# Connectors.net
KiCad netlist of a schematic drawn in Altium Designer
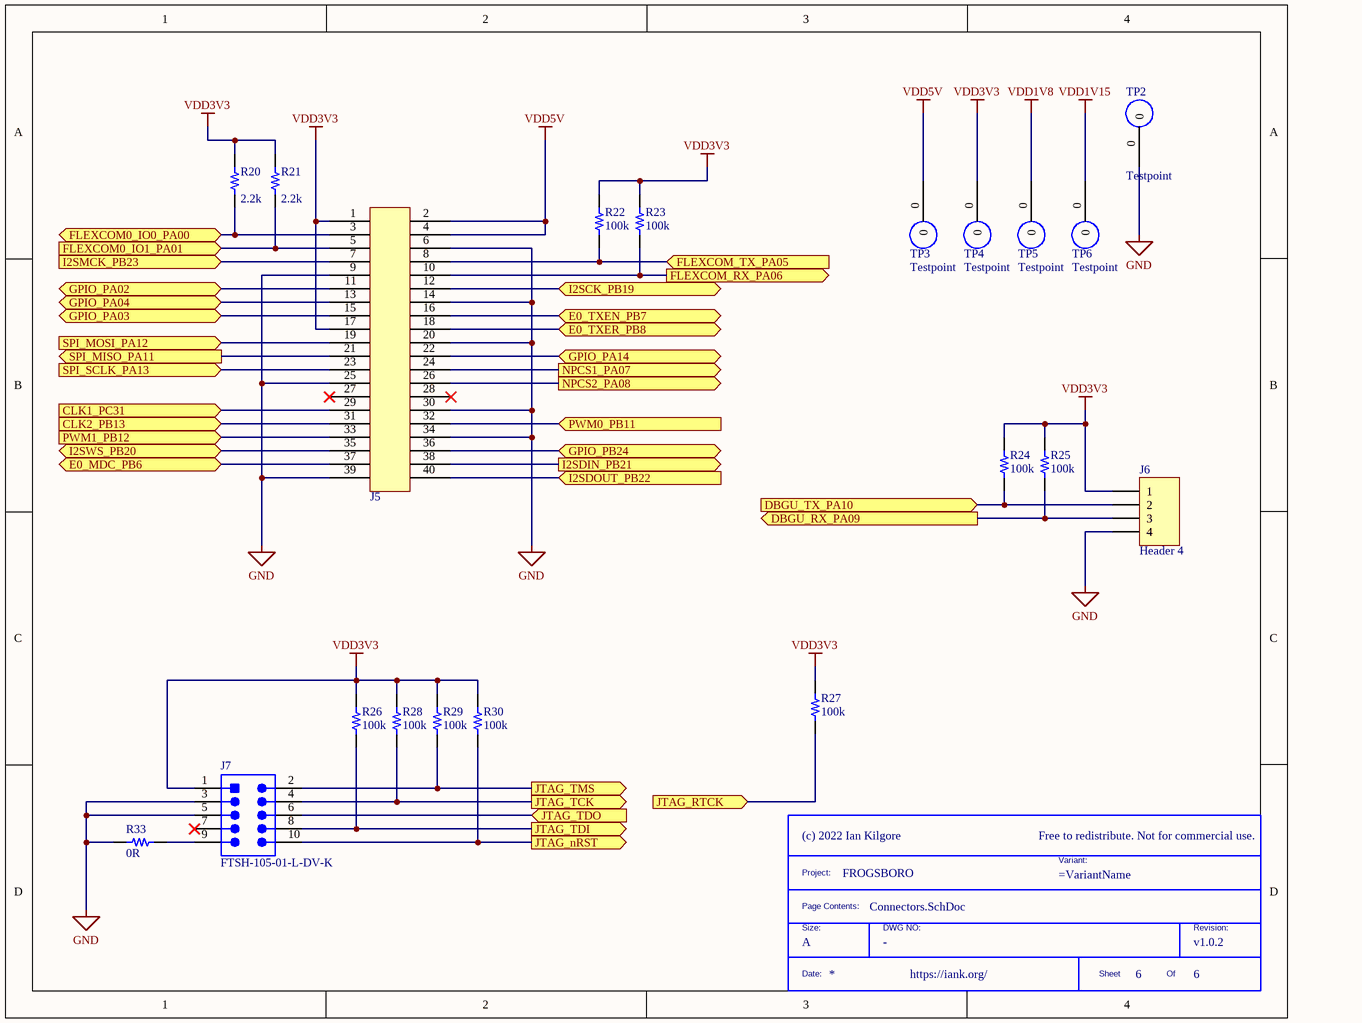
[diagram p0: Connectors.SchDoc]

(export (version "E")
  (design (tool "Eeschema 10.0.6"))
  (components
    (comp (ref "J5")
      (value "DF23C-40DP-0.5V(92)")
      (footprint "FROGSBORO:DF23C-40DP-0.5V(92)")
      (description "0.5mm Pitch Low-Profile (H=1.5mm) Board to Board / FPC to Board Connectors")
      (fields (field (name "MANUFACTURER") "Hirose"))
      (libsource (lib "FROGSBORO") (part "DF23C-40DP-0.5V(92)"))
    )
    (comp (ref "J6")
      (value "Header 4")
      (footprint "HDR1X4")
      (description "Header, 4-Pin")
      (fields (field (name "PUBLISHER") "Altium Limited"))
      (libsource (lib "Miscellaneous Connectors") (part "Header 4"))
    )
    (comp (ref "J7")
      (value "FTSH-105-01-L-DV-K")
      (footprint "SMTC-FTSH-105-01-L-DV-K_V")
      (description "Male Header, Pitch 1.27 mm, 2 x 5 Position, Height 6.25 mm")
      (fields (field (name "MANUFACTURER") "Samtec"))
      (libsource (lib "Altium Content Vault") (part "CN-2P-M-R10"))
    )
    (comp (ref "R20")
      (value "2.2k")
      (footprint "RES 0402_1005")
      (description "RES SMD 2.2K OHM 1% 1/5W 0402")
      (fields (field (name "PART NUMBER") "RCS04022K20FKED"))
      (libsource (lib "Celestial Altium Library - altium_library") (part "Resistor"))
    )
    (comp (ref "R21")
      (value "2.2k")
      (footprint "RES 0402_1005")
      (description "RES SMD 2.2K OHM 1% 1/5W 0402")
      (fields (field (name "PART NUMBER") "RCS04022K20FKED"))
      (libsource (lib "Celestial Altium Library - altium_library") (part "Resistor"))
    )
    (comp (ref "R22")
      (value "100k")
      (footprint "RES 0402_1005")
      (description "RES SMD 100K OHM 1% 1/16W 0402")
      (fields (field (name "PART NUMBER") "CRCW0402100KFKEDC") (field (name "MANUFACTURER") "Vishay Dale"))
      (libsource (lib "Celestial Altium Library - altium_library") (part "Resistor"))
    )
    (comp (ref "R23")
      (value "100k")
      (footprint "RES 0402_1005")
      (description "RES SMD 100K OHM 1% 1/16W 0402")
      (fields (field (name "PART NUMBER") "CRCW0402100KFKEDC") (field (name "MANUFACTURER") "Vishay Dale"))
      (libsource (lib "Celestial Altium Library - altium_library") (part "Resistor"))
    )
    (comp (ref "R24")
      (value "100k")
      (footprint "RES 0402_1005")
      (description "RES SMD 100K OHM 1% 1/16W 0402")
      (fields (field (name "PART NUMBER") "CRCW0402100KFKEDC") (field (name "MANUFACTURER") "Vishay Dale"))
      (libsource (lib "Celestial Altium Library - altium_library") (part "Resistor"))
    )
    (comp (ref "R25")
      (value "100k")
      (footprint "RES 0402_1005")
      (description "RES SMD 100K OHM 1% 1/16W 0402")
      (fields (field (name "PART NUMBER") "CRCW0402100KFKEDC") (field (name "MANUFACTURER") "Vishay Dale"))
      (libsource (lib "Celestial Altium Library - altium_library") (part "Resistor"))
    )
    (comp (ref "R26")
      (value "100k")
      (footprint "RES 0402_1005")
      (description "RES SMD 100K OHM 1% 1/16W 0402")
      (fields (field (name "PART NUMBER") "CRCW0402100KFKEDC") (field (name "MANUFACTURER") "Vishay Dale"))
      (libsource (lib "Celestial Altium Library - altium_library") (part "Resistor"))
    )
    (comp (ref "R27")
      (value "100k")
      (footprint "RES 0402_1005")
      (description "RES SMD 100K OHM 1% 1/16W 0402")
      (fields (field (name "PART NUMBER") "CRCW0402100KFKEDC") (field (name "MANUFACTURER") "Vishay Dale"))
      (libsource (lib "Celestial Altium Library - altium_library") (part "Resistor"))
    )
    (comp (ref "R28")
      (value "100k")
      (footprint "RES 0402_1005")
      (description "RES SMD 100K OHM 1% 1/16W 0402")
      (fields (field (name "PART NUMBER") "CRCW0402100KFKEDC") (field (name "MANUFACTURER") "Vishay Dale"))
      (libsource (lib "Celestial Altium Library - altium_library") (part "Resistor"))
    )
    (comp (ref "R29")
      (value "100k")
      (footprint "RES 0402_1005")
      (description "RES SMD 100K OHM 1% 1/16W 0402")
      (fields (field (name "PART NUMBER") "CRCW0402100KFKEDC") (field (name "MANUFACTURER") "Vishay Dale"))
      (libsource (lib "Celestial Altium Library - altium_library") (part "Resistor"))
    )
    (comp (ref "R30")
      (value "100k")
      (footprint "RES 0402_1005")
      (description "RES SMD 100K OHM 1% 1/16W 0402")
      (fields (field (name "PART NUMBER") "CRCW0402100KFKEDC") (field (name "MANUFACTURER") "Vishay Dale"))
      (libsource (lib "Celestial Altium Library - altium_library") (part "Resistor"))
    )
    (comp (ref "R33")
      (value "0R")
      (footprint "RES 0402_1005")
      (description "RES SMD 0 OHM JUMPER 1/16W 0402")
      (fields
        (field (name "PART NUMBER") "CRG0402ZR")
        (field (name "MANUFACTURER") "TE Connectivity Passive Product")
      )
      (libsource (lib "Celestial Altium Library - altium_library") (part "Resistor"))
    )
    (comp (ref "TP2")
      (value "Testpoint")
      (footprint "FROGSBORO:Testpoint")
      (libsource (lib "FROGSBORO") (part "Testpoint"))
    )
    (comp (ref "TP3")
      (value "Testpoint")
      (footprint "FROGSBORO:Testpoint")
      (libsource (lib "FROGSBORO") (part "Testpoint"))
    )
    (comp (ref "TP4")
      (value "Testpoint")
      (footprint "FROGSBORO:Testpoint")
      (libsource (lib "FROGSBORO") (part "Testpoint"))
    )
    (comp (ref "TP5")
      (value "Testpoint")
      (footprint "FROGSBORO:Testpoint")
      (libsource (lib "FROGSBORO") (part "Testpoint"))
    )
    (comp (ref "TP6")
      (value "Testpoint")
      (footprint "FROGSBORO:Testpoint")
      (libsource (lib "FROGSBORO") (part "Testpoint"))
    )
  )
  (nets
    (net (code "1") (name "/CLK1_PC31") (class "Default") (node (ref "J5") (pin "29") (pintype "passive")))
    (net (code "2") (name "/CLK2_PB13") (class "Default") (node (ref "J5") (pin "31") (pintype "passive")))
    (net (code "3") (name "/DBGU_RX_PA09") (class "Default")
      (node (ref "J6") (pin "3") (pinfunction "3_3") (pintype "passive"))
      (node (ref "R25") (pin "1") (pinfunction "1_1") (pintype "passive"))
    )
    (net (code "4") (name "/DBGU_TX_PA10") (class "Default")
      (node (ref "J6") (pin "2") (pinfunction "2_2") (pintype "passive"))
      (node (ref "R24") (pin "1") (pinfunction "1_1") (pintype "passive"))
    )
    (net (code "5") (name "/E0_MDC_PB6") (class "Default") (node (ref "J5") (pin "37") (pintype "passive")))
    (net (code "6") (name "/E0_TXEN_PB7") (class "Default") (node (ref "J5") (pin "16") (pintype "passive")))
    (net (code "7") (name "/E0_TXER_PB8") (class "Default") (node (ref "J5") (pin "18") (pintype "passive")))
    (net (code "8") (name "/FLEXCOM0_IO0_PA00") (class "Default")
      (node (ref "J5") (pin "3") (pintype "passive"))
      (node (ref "R20") (pin "1") (pinfunction "1_1") (pintype "passive"))
    )
    (net (code "9") (name "/FLEXCOM0_IO1_PA01") (class "Default")
      (node (ref "J5") (pin "5") (pintype "passive"))
      (node (ref "R21") (pin "1") (pinfunction "1_1") (pintype "passive"))
    )
    (net (code "10") (name "/FLEXCOM_RX_PA06") (class "Default")
      (node (ref "J5") (pin "10") (pintype "passive"))
      (node (ref "R23") (pin "1") (pinfunction "1_1") (pintype "passive"))
    )
    (net (code "11") (name "/FLEXCOM_TX_PA05") (class "Default")
      (node (ref "J5") (pin "8") (pintype "passive"))
      (node (ref "R22") (pin "1") (pinfunction "1_1") (pintype "passive"))
    )
    (net (code "12") (name "/GPIO_PA02") (class "Default") (node (ref "J5") (pin "11") (pintype "passive")))
    (net (code "13") (name "/GPIO_PA03") (class "Default") (node (ref "J5") (pin "15") (pintype "passive")))
    (net (code "14") (name "/GPIO_PA04") (class "Default") (node (ref "J5") (pin "13") (pintype "passive")))
    (net (code "15") (name "/GPIO_PA14") (class "Default") (node (ref "J5") (pin "22") (pintype "passive")))
    (net (code "16") (name "/GPIO_PB24") (class "Default") (node (ref "J5") (pin "36") (pintype "passive")))
    (net (code "17") (name "/I2SCK_PB19") (class "Default") (node (ref "J5") (pin "12") (pintype "passive")))
    (net (code "18") (name "/I2SDIN_PB21") (class "Default") (node (ref "J5") (pin "38") (pintype "passive")))
    (net (code "19") (name "/I2SDOUT_PB22") (class "Default")
      (node (ref "J5") (pin "40") (pintype "passive"))
    )
    (net (code "20") (name "/I2SMCK_PB23") (class "Default") (node (ref "J5") (pin "7") (pintype "passive")))
    (net (code "21") (name "/I2SWS_PB20") (class "Default") (node (ref "J5") (pin "35") (pintype "passive")))
    (net (code "22") (name "/JTAG_RTCK") (class "Default")
      (node (ref "R27") (pin "1") (pinfunction "1_1") (pintype "passive"))
    )
    (net (code "23") (name "/JTAG_TCK") (class "Default")
      (node (ref "J7") (pin "4") (pinfunction "4_4") (pintype "passive"))
      (node (ref "R28") (pin "1") (pinfunction "1_1") (pintype "passive"))
    )
    (net (code "24") (name "/JTAG_TDI") (class "Default")
      (node (ref "J7") (pin "8") (pinfunction "8_8") (pintype "passive"))
      (node (ref "R26") (pin "1") (pinfunction "1_1") (pintype "passive"))
    )
    (net (code "25") (name "/JTAG_TDO") (class "Default")
      (node (ref "J7") (pin "6") (pinfunction "6_6") (pintype "passive"))
    )
    (net (code "26") (name "/JTAG_TMS") (class "Default")
      (node (ref "J7") (pin "2") (pinfunction "2_2") (pintype "passive"))
      (node (ref "R29") (pin "1") (pinfunction "1_1") (pintype "passive"))
    )
    (net (code "27") (name "/JTAG_nRST") (class "Default")
      (node (ref "J7") (pin "10") (pinfunction "10_10") (pintype "passive"))
      (node (ref "R30") (pin "1") (pinfunction "1_1") (pintype "passive"))
    )
    (net (code "28") (name "/NPCS1_PA07") (class "Default") (node (ref "J5") (pin "24") (pintype "passive")))
    (net (code "29") (name "/NPCS2_PA08") (class "Default") (node (ref "J5") (pin "26") (pintype "passive")))
    (net (code "30") (name "/PWM0_PB11") (class "Default") (node (ref "J5") (pin "32") (pintype "passive")))
    (net (code "31") (name "/PWM1_PB12") (class "Default") (node (ref "J5") (pin "33") (pintype "passive")))
    (net (code "32") (name "/SPI_MISO_PA11") (class "Default")
      (node (ref "J5") (pin "21") (pintype "passive"))
    )
    (net (code "33") (name "/SPI_MOSI_PA12") (class "Default")
      (node (ref "J5") (pin "19") (pintype "passive"))
    )
    (net (code "34") (name "/SPI_SCLK_PA13") (class "Default")
      (node (ref "J5") (pin "23") (pintype "passive"))
    )
    (net (code "35") (name "GND") (class "Default")
      (node (ref "J5") (pin "14") (pintype "passive"))
      (node (ref "J5") (pin "20") (pintype "passive"))
      (node (ref "J5") (pin "25") (pintype "passive"))
      (node (ref "J5") (pin "30") (pintype "passive"))
      (node (ref "J5") (pin "34") (pintype "passive"))
      (node (ref "J5") (pin "39") (pintype "passive"))
      (node (ref "J5") (pin "6") (pintype "passive"))
      (node (ref "J5") (pin "9") (pintype "passive"))
      (node (ref "J6") (pin "4") (pinfunction "4_4") (pintype "passive"))
      (node (ref "J7") (pin "3") (pinfunction "3_3") (pintype "passive"))
      (node (ref "J7") (pin "5") (pinfunction "5_5") (pintype "passive"))
      (node (ref "R33") (pin "2") (pinfunction "2_2") (pintype "passive"))
      (node (ref "TP2") (pin "0") (pinfunction "0_0") (pintype "passive"))
    )
    (net (code "36") (name "Net-(J7-Pad9)") (class "Default")
      (node (ref "J7") (pin "9") (pinfunction "9_9") (pintype "passive"))
      (node (ref "R33") (pin "1") (pinfunction "1_1") (pintype "passive"))
    )
    (net (code "37") (name "VDD1V8") (class "Default")
      (node (ref "TP5") (pin "0") (pinfunction "0_0") (pintype "passive"))
    )
    (net (code "38") (name "VDD1V15") (class "Default")
      (node (ref "TP6") (pin "0") (pinfunction "0_0") (pintype "passive"))
    )
    (net (code "39") (name "VDD3V3") (class "Default")
      (node (ref "J5") (pin "1") (pintype "passive"))
      (node (ref "J5") (pin "17") (pintype "passive"))
      (node (ref "J6") (pin "1") (pinfunction "1_1") (pintype "passive"))
      (node (ref "J7") (pin "1") (pinfunction "1_1") (pintype "passive"))
      (node (ref "R20") (pin "2") (pinfunction "2_2") (pintype "passive"))
      (node (ref "R21") (pin "2") (pinfunction "2_2") (pintype "passive"))
      (node (ref "R22") (pin "2") (pinfunction "2_2") (pintype "passive"))
      (node (ref "R23") (pin "2") (pinfunction "2_2") (pintype "passive"))
      (node (ref "R24") (pin "2") (pinfunction "2_2") (pintype "passive"))
      (node (ref "R25") (pin "2") (pinfunction "2_2") (pintype "passive"))
      (node (ref "R26") (pin "2") (pinfunction "2_2") (pintype "passive"))
      (node (ref "R27") (pin "2") (pinfunction "2_2") (pintype "passive"))
      (node (ref "R28") (pin "2") (pinfunction "2_2") (pintype "passive"))
      (node (ref "R29") (pin "2") (pinfunction "2_2") (pintype "passive"))
      (node (ref "R30") (pin "2") (pinfunction "2_2") (pintype "passive"))
      (node (ref "TP4") (pin "0") (pinfunction "0_0") (pintype "passive"))
    )
    (net (code "40") (name "VDD5V") (class "Default")
      (node (ref "J5") (pin "2") (pintype "passive"))
      (node (ref "J5") (pin "4") (pintype "passive"))
      (node (ref "TP3") (pin "0") (pinfunction "0_0") (pintype "passive"))
    )
    (net (code "41") (name "unconnected-(J5-Pad27)") (class "Default")
      (node (ref "J5") (pin "27") (pintype "passive+no_connect"))
    )
    (net (code "42") (name "unconnected-(J5-Pad28)") (class "Default")
      (node (ref "J5") (pin "28") (pintype "passive+no_connect"))
    )
    (net (code "43") (name "unconnected-(J7-Pad7)") (class "Default")
      (node (ref "J7") (pin "7") (pinfunction "7_7") (pintype "passive+no_connect"))
    )
  )
)
